# MMA8452QT.net
KiCad netlist of a schematic drawn in Altium Designer
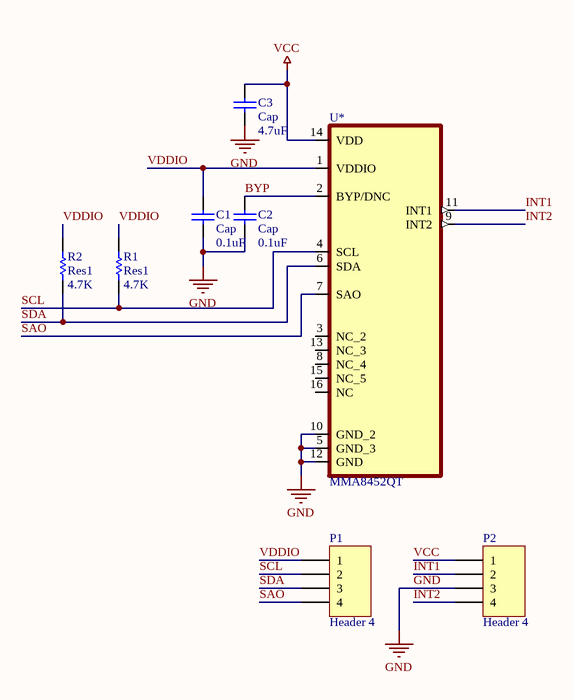
[diagram p0: MMA8452QT.SchDoc]

(export (version "E")
  (design (tool "Eeschema 10.0.6"))
  (components
    (comp (ref "C1")
      (value "Cap")
      (footprint "RAD-0.3")
      (description "Capacitor")
      (fields (field (name "ALTIUM_VALUE") "0.1uF") (field (name "PUBLISHER") "Altium Limited"))
      (libsource (lib "Miscellaneous Devices") (part "Cap"))
    )
    (comp (ref "C2")
      (value "Cap")
      (footprint "RAD-0.3")
      (description "Capacitor")
      (fields (field (name "ALTIUM_VALUE") "0.1uF") (field (name "PUBLISHER") "Altium Limited"))
      (libsource (lib "Miscellaneous Devices") (part "Cap"))
    )
    (comp (ref "C3")
      (value "Cap")
      (footprint "RAD-0.3")
      (description "Capacitor")
      (fields (field (name "ALTIUM_VALUE") "4.7uF") (field (name "PUBLISHER") "Altium Limited"))
      (libsource (lib "Miscellaneous Devices") (part "Cap"))
    )
    (comp (ref "P1")
      (value "Header 4")
      (footprint "HDR1X4")
      (description "Header, 4-Pin")
      (fields (field (name "PUBLISHER") "Altium Limited"))
      (libsource (lib "Miscellaneous Connectors") (part "Header 4"))
    )
    (comp (ref "P2")
      (value "Header 4")
      (footprint "HDR1X4")
      (description "Header, 4-Pin")
      (fields (field (name "PUBLISHER") "Altium Limited"))
      (libsource (lib "Miscellaneous Connectors") (part "Header 4"))
    )
    (comp (ref "R1")
      (value "Res1")
      (footprint "AXIAL-0.3")
      (description "Resistor")
      (fields (field (name "ALTIUM_VALUE") "4.7K") (field (name "PUBLISHER") "Altium Limited"))
      (libsource (lib "Miscellaneous Devices") (part "Res1"))
    )
    (comp (ref "R2")
      (value "Res1")
      (footprint "AXIAL-0.3")
      (description "Resistor")
      (fields (field (name "ALTIUM_VALUE") "4.7K") (field (name "PUBLISHER") "Altium Limited"))
      (libsource (lib "Miscellaneous Devices") (part "Res1"))
    )
    (comp (ref "U*")
      (value "MMA8452QT")
      (footprint "MMA8452QT")
      (libsource (lib "Accelerometres") (part "MMA8452QT"))
    )
  )
  (nets
    (net (code "1") (name "/BYP") (class "Default")
      (node (ref "C2") (pin "2") (pinfunction "2_2") (pintype "passive"))
      (node (ref "U*") (pin "2") (pinfunction "BYP/DNC_2") (pintype "passive"))
    )
    (net (code "2") (name "/INT1") (class "Default")
      (node (ref "P2") (pin "2") (pinfunction "2_2") (pintype "passive"))
      (node (ref "U*") (pin "11") (pinfunction "INT1_11") (pintype "output"))
    )
    (net (code "3") (name "/INT2") (class "Default")
      (node (ref "P2") (pin "4") (pinfunction "4_4") (pintype "passive"))
      (node (ref "U*") (pin "9") (pinfunction "INT2_9") (pintype "output"))
    )
    (net (code "4") (name "/SAO") (class "Default")
      (node (ref "P1") (pin "4") (pinfunction "4_4") (pintype "passive"))
      (node (ref "U*") (pin "7") (pinfunction "SAO_7") (pintype "passive"))
    )
    (net (code "5") (name "/SCL") (class "Default")
      (node (ref "P1") (pin "2") (pinfunction "2_2") (pintype "passive"))
      (node (ref "R1") (pin "1") (pinfunction "1_1") (pintype "passive"))
      (node (ref "U*") (pin "4") (pinfunction "SCL_4") (pintype "passive"))
    )
    (net (code "6") (name "/SDA") (class "Default")
      (node (ref "P1") (pin "3") (pinfunction "3_3") (pintype "passive"))
      (node (ref "R2") (pin "1") (pinfunction "1_1") (pintype "passive"))
      (node (ref "U*") (pin "6") (pinfunction "SDA_6") (pintype "passive"))
    )
    (net (code "7") (name "/VDDIO") (class "Default")
      (node (ref "C1") (pin "2") (pinfunction "2_2") (pintype "passive"))
      (node (ref "P1") (pin "1") (pinfunction "1_1") (pintype "passive"))
      (node (ref "R1") (pin "2") (pinfunction "2_2") (pintype "passive"))
      (node (ref "R2") (pin "2") (pinfunction "2_2") (pintype "passive"))
      (node (ref "U*") (pin "1") (pinfunction "VDDIO_1") (pintype "power_in"))
    )
    (net (code "8") (name "GND") (class "Default")
      (node (ref "C1") (pin "1") (pinfunction "1_1") (pintype "passive"))
      (node (ref "C2") (pin "1") (pinfunction "1_1") (pintype "passive"))
      (node (ref "C3") (pin "1") (pinfunction "1_1") (pintype "passive"))
      (node (ref "P2") (pin "3") (pinfunction "3_3") (pintype "passive"))
      (node (ref "U*") (pin "10") (pinfunction "GND_2_10") (pintype "passive"))
      (node (ref "U*") (pin "12") (pinfunction "GND_12") (pintype "passive"))
      (node (ref "U*") (pin "5") (pinfunction "GND_3_5") (pintype "passive"))
    )
    (net (code "9") (name "VCC") (class "Default")
      (node (ref "C3") (pin "2") (pinfunction "2_2") (pintype "passive"))
      (node (ref "P2") (pin "1") (pinfunction "1_1") (pintype "passive"))
      (node (ref "U*") (pin "14") (pinfunction "VDD_14") (pintype "power_in"))
    )
    (net (code "10") (name "unconnected-(U*-NC-Pad16)") (class "Default")
      (node (ref "U*") (pin "16") (pinfunction "NC_16") (pintype "passive"))
    )
    (net (code "11") (name "unconnected-(U*-NC_2-Pad3)") (class "Default")
      (node (ref "U*") (pin "3") (pinfunction "NC_2_3") (pintype "passive"))
    )
    (net (code "12") (name "unconnected-(U*-NC_3-Pad13)") (class "Default")
      (node (ref "U*") (pin "13") (pinfunction "NC_3_13") (pintype "passive"))
    )
    (net (code "13") (name "unconnected-(U*-NC_4-Pad8)") (class "Default")
      (node (ref "U*") (pin "8") (pinfunction "NC_4_8") (pintype "passive"))
    )
    (net (code "14") (name "unconnected-(U*-NC_5-Pad15)") (class "Default")
      (node (ref "U*") (pin "15") (pinfunction "NC_5_15") (pintype "passive"))
    )
  )
)
